# LMD18200_24.net
KiCad netlist of a schematic drawn in EAGLE
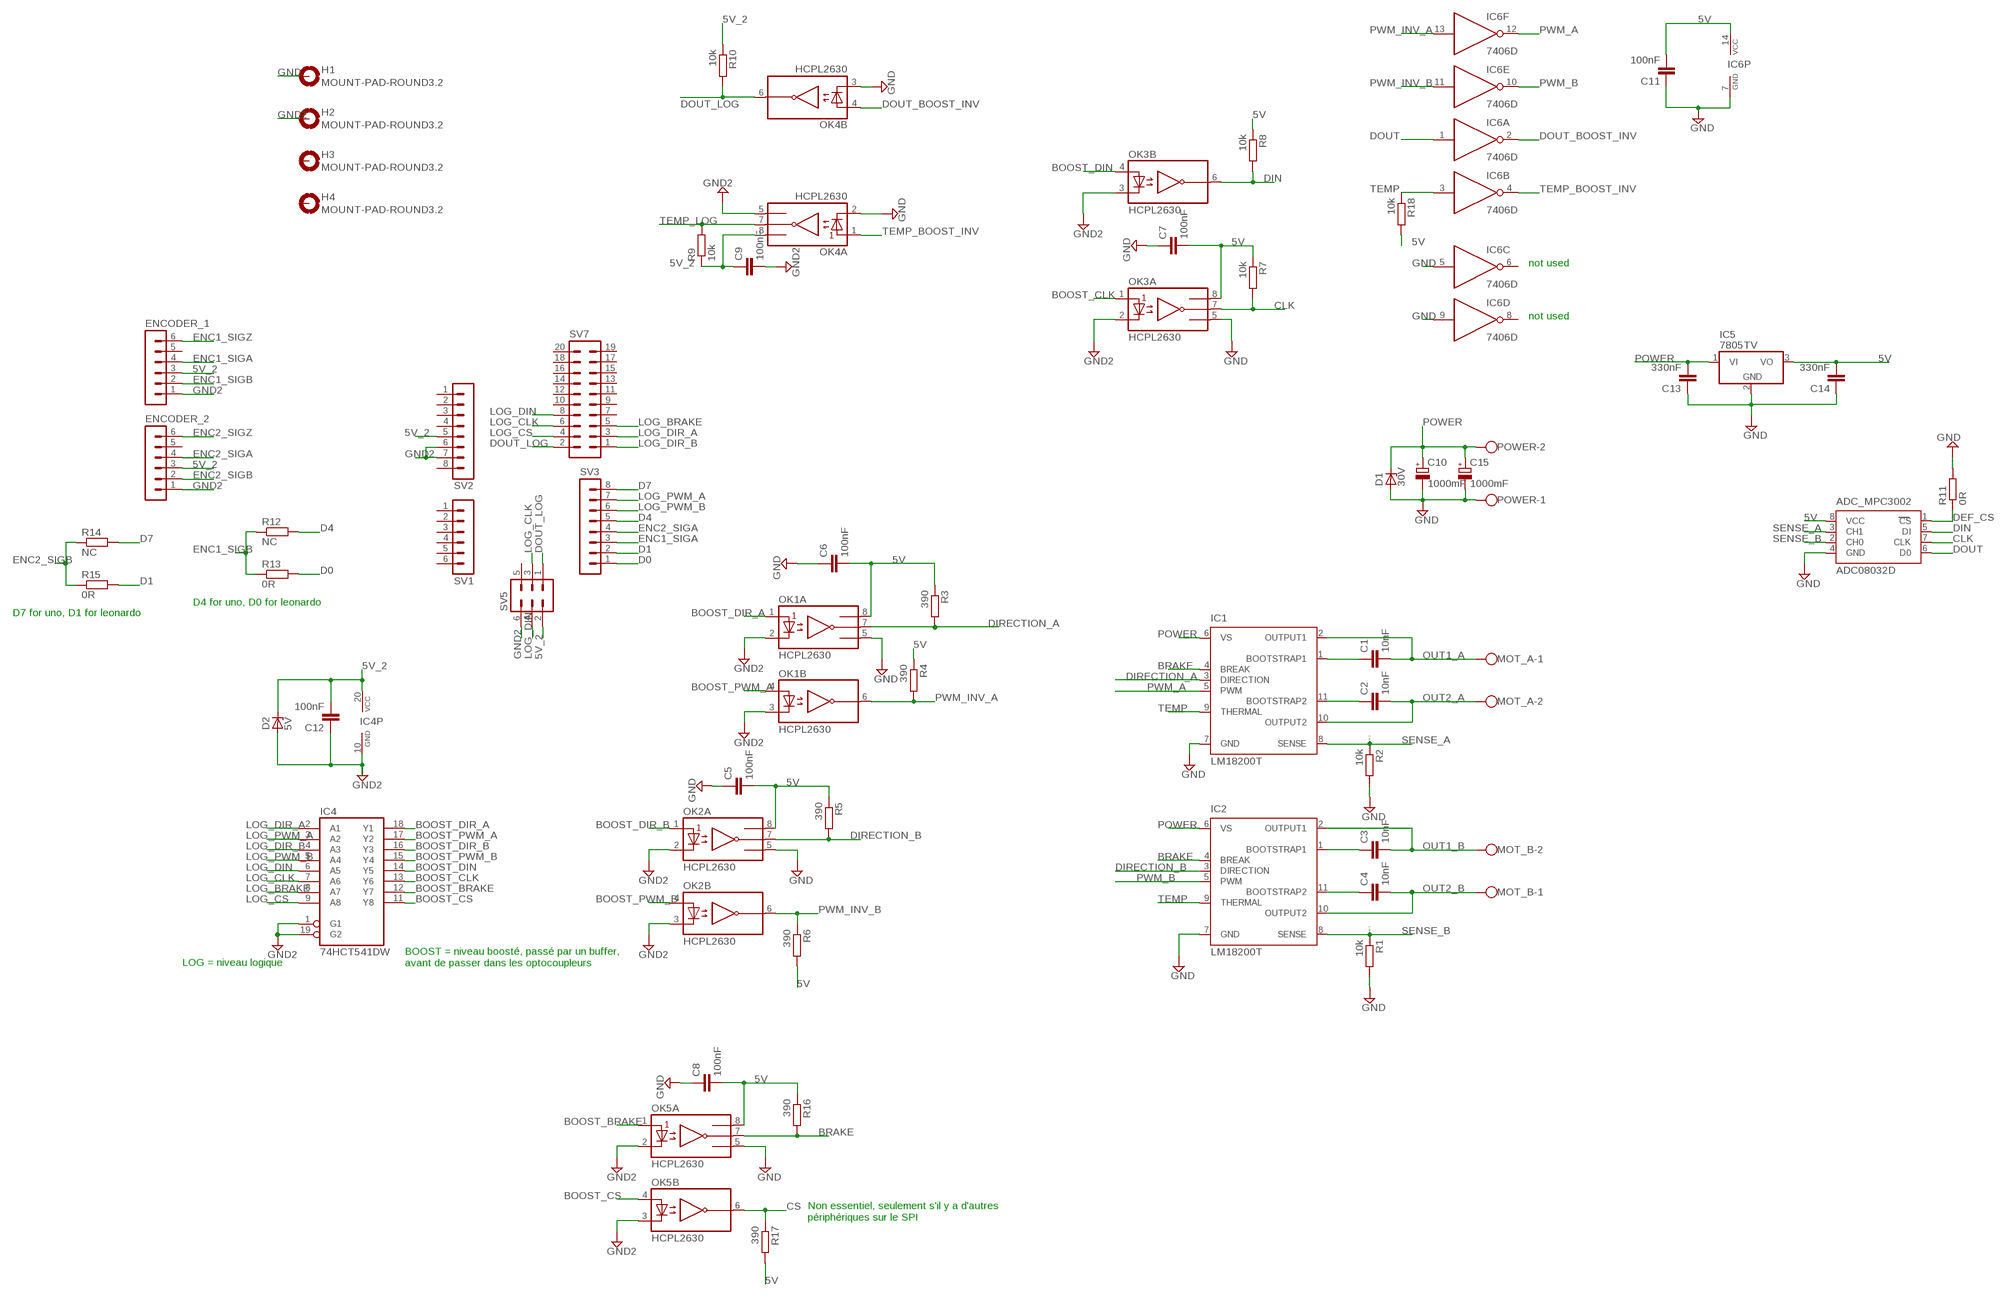
[diagram p0: schematic, sheet 1]

(export (version "E")
  (design (tool "Eeschema 10.0.6"))
  (components
    (comp (ref "ADC_MPC3002")
      (value "ADC08032D")
      (footprint "eagle-import:SO08")
      (libsource (lib "eagle-import") (part "ADC08032D"))
    )
    (comp (ref "C1")
      (value "10nF")
      (footprint "eagle-import:C2.5-2")
      (libsource (lib "eagle-import") (part "C2.5/2"))
    )
    (comp (ref "C2")
      (value "10nF")
      (footprint "eagle-import:C2.5-2")
      (libsource (lib "eagle-import") (part "C2.5/2"))
    )
    (comp (ref "C3")
      (value "10nF")
      (footprint "eagle-import:C2.5-2")
      (libsource (lib "eagle-import") (part "C2.5/2"))
    )
    (comp (ref "C4")
      (value "10nF")
      (footprint "eagle-import:C2.5-2")
      (libsource (lib "eagle-import") (part "C2.5/2"))
    )
    (comp (ref "C5")
      (value "100nF")
      (footprint "eagle-import:C2.5-2")
      (libsource (lib "eagle-import") (part "C2.5/2"))
    )
    (comp (ref "C6")
      (value "100nF")
      (footprint "eagle-import:C2.5-2")
      (libsource (lib "eagle-import") (part "C2.5/2"))
    )
    (comp (ref "C7")
      (value "100nF")
      (footprint "eagle-import:C2.5-2")
      (libsource (lib "eagle-import") (part "C2.5/2"))
    )
    (comp (ref "C8")
      (value "100nF")
      (footprint "eagle-import:C2.5-2")
      (libsource (lib "eagle-import") (part "C2.5/2"))
    )
    (comp (ref "C9")
      (value "100nF")
      (footprint "eagle-import:C2.5-2")
      (libsource (lib "eagle-import") (part "C2.5/2"))
    )
    (comp (ref "C10")
      (value "1000mF")
      (footprint "eagle-import:E5-13")
      (libsource (lib "eagle-import") (part "CPOL-EUE5-13"))
    )
    (comp (ref "C11")
      (value "100nF")
      (footprint "eagle-import:C0805")
      (libsource (lib "eagle-import") (part "C-EUC0805"))
    )
    (comp (ref "C12")
      (value "100nF")
      (footprint "eagle-import:C2.5-2")
      (libsource (lib "eagle-import") (part "C2.5/2"))
    )
    (comp (ref "C13")
      (value "330nF")
      (footprint "eagle-import:C2.5-2")
      (libsource (lib "eagle-import") (part "C2.5/2"))
    )
    (comp (ref "C14")
      (value "330nF")
      (footprint "eagle-import:C2.5-2")
      (libsource (lib "eagle-import") (part "C2.5/2"))
    )
    (comp (ref "C15")
      (value "1000mF")
      (footprint "eagle-import:E5-13")
      (libsource (lib "eagle-import") (part "CPOL-EUE5-13"))
    )
    (comp (ref "D1")
      (value "30V")
      (footprint "eagle-import:SOD80C")
      (libsource (lib "eagle-import") (part "ZENER-DIODESOD80C"))
    )
    (comp (ref "D2")
      (value "5V")
      (footprint "eagle-import:SOD80C")
      (libsource (lib "eagle-import") (part "ZENER-DIODESOD80C"))
    )
    (comp (ref "ENCODER_1")
      (value "MA06-1")
      (footprint "eagle-import:MA06-1")
      (libsource (lib "eagle-import") (part "MA06-1"))
    )
    (comp (ref "ENCODER_2")
      (value "MA06-1")
      (footprint "eagle-import:MA06-1")
      (libsource (lib "eagle-import") (part "MA06-1"))
    )
    (comp (ref "H1")
      (value "MOUNT-PAD-ROUND3.2")
      (footprint "eagle-import:3,2-PAD")
      (libsource (lib "eagle-import") (part "MOUNT-PAD-ROUND3.2"))
    )
    (comp (ref "H2")
      (value "MOUNT-PAD-ROUND3.2")
      (footprint "eagle-import:3,2-PAD")
      (libsource (lib "eagle-import") (part "MOUNT-PAD-ROUND3.2"))
    )
    (comp (ref "H3")
      (value "MOUNT-PAD-ROUND3.2")
      (footprint "eagle-import:3,2-PAD")
      (libsource (lib "eagle-import") (part "MOUNT-PAD-ROUND3.2"))
    )
    (comp (ref "H4")
      (value "MOUNT-PAD-ROUND3.2")
      (footprint "eagle-import:3,2-PAD")
      (libsource (lib "eagle-import") (part "MOUNT-PAD-ROUND3.2"))
    )
    (comp (ref "IC1")
      (value "LM18200T")
      (footprint "eagle-import:TO-220-11")
      (libsource (lib "eagle-import") (part "LM18200T"))
    )
    (comp (ref "IC2")
      (value "LM18200T")
      (footprint "eagle-import:TO-220-11")
      (libsource (lib "eagle-import") (part "LM18200T"))
    )
    (comp (ref "IC4")
      (value "74HCT541DW")
      (footprint "eagle-import:SO20W")
      (libsource (lib "eagle-import") (part "74541DWHCT"))
    )
    (comp (ref "IC5")
      (value "7805TV")
      (footprint "eagle-import:TO220V")
      (libsource (lib "eagle-import") (part "78TV05"))
    )
    (comp (ref "IC6")
      (value "7406D")
      (footprint "eagle-import:SO14")
      (libsource (lib "eagle-import") (part "7406D"))
    )
    (comp (ref "MOT_A")
      (value "W237-102")
      (footprint "eagle-import:W237-102")
      (fields (field (name "MPN") "237-102"))
      (libsource (lib "eagle-import") (part "W237-102"))
    )
    (comp (ref "MOT_B")
      (value "W237-102")
      (footprint "eagle-import:W237-102")
      (fields (field (name "MPN") "237-102"))
      (libsource (lib "eagle-import") (part "W237-102"))
    )
    (comp (ref "OK1")
      (value "HCPL2630")
      (footprint "eagle-import:DIL08")
      (fields (field (name "MF") "AGILENT TECHNOLOGIES") (field (name "MPN") "HCPL-2630-000E"))
      (libsource (lib "eagle-import") (part "HCPL2630"))
    )
    (comp (ref "OK2")
      (value "HCPL2630")
      (footprint "eagle-import:DIL08")
      (fields (field (name "MF") "AGILENT TECHNOLOGIES") (field (name "MPN") "HCPL-2630-000E"))
      (libsource (lib "eagle-import") (part "HCPL2630"))
    )
    (comp (ref "OK3")
      (value "HCPL2630")
      (footprint "eagle-import:DIL08")
      (fields (field (name "MF") "AGILENT TECHNOLOGIES") (field (name "MPN") "HCPL-2630-000E"))
      (libsource (lib "eagle-import") (part "HCPL2630"))
    )
    (comp (ref "OK4")
      (value "HCPL2630")
      (footprint "eagle-import:DIL08")
      (fields (field (name "MF") "AGILENT TECHNOLOGIES") (field (name "MPN") "HCPL-2630-000E"))
      (libsource (lib "eagle-import") (part "HCPL2630"))
    )
    (comp (ref "OK5")
      (value "HCPL2630")
      (footprint "eagle-import:DIL08")
      (fields (field (name "MF") "AGILENT TECHNOLOGIES") (field (name "MPN") "HCPL-2630-000E"))
      (libsource (lib "eagle-import") (part "HCPL2630"))
    )
    (comp (ref "POWER")
      (value "W237-102")
      (footprint "eagle-import:W237-102")
      (fields (field (name "MPN") "237-102"))
      (libsource (lib "eagle-import") (part "W237-102"))
    )
    (comp (ref "R1")
      (value "10k")
      (footprint "eagle-import:R0805")
      (libsource (lib "eagle-import") (part "R"))
    )
    (comp (ref "R2")
      (value "10k")
      (footprint "eagle-import:R0805")
      (libsource (lib "eagle-import") (part "R"))
    )
    (comp (ref "R3")
      (value "390")
      (footprint "eagle-import:R0805")
      (libsource (lib "eagle-import") (part "R-EU_R0805"))
    )
    (comp (ref "R4")
      (value "390")
      (footprint "eagle-import:R0805")
      (libsource (lib "eagle-import") (part "R-EU_R0805"))
    )
    (comp (ref "R5")
      (value "390")
      (footprint "eagle-import:R0805")
      (libsource (lib "eagle-import") (part "R-EU_R0805"))
    )
    (comp (ref "R6")
      (value "390")
      (footprint "eagle-import:R0805")
      (libsource (lib "eagle-import") (part "R-EU_R0805"))
    )
    (comp (ref "R7")
      (value "10k")
      (footprint "eagle-import:R0805")
      (libsource (lib "eagle-import") (part "R-EU_R0805"))
    )
    (comp (ref "R8")
      (value "10k")
      (footprint "eagle-import:R0805")
      (libsource (lib "eagle-import") (part "R-EU_R0805"))
    )
    (comp (ref "R9")
      (value "10k")
      (footprint "eagle-import:R0805")
      (libsource (lib "eagle-import") (part "R-EU_R0805"))
    )
    (comp (ref "R10")
      (value "10k")
      (footprint "eagle-import:R0805")
      (libsource (lib "eagle-import") (part "R-EU_R0805"))
    )
    (comp (ref "R11")
      (value "0R")
      (footprint "eagle-import:R0805")
      (libsource (lib "eagle-import") (part "R"))
    )
    (comp (ref "R12")
      (value "NC")
      (footprint "eagle-import:R0805")
      (libsource (lib "eagle-import") (part "R-EU_R0805"))
    )
    (comp (ref "R13")
      (value "0R")
      (footprint "eagle-import:R0805")
      (libsource (lib "eagle-import") (part "R-EU_R0805"))
    )
    (comp (ref "R14")
      (value "NC")
      (footprint "eagle-import:R0805")
      (libsource (lib "eagle-import") (part "R-EU_R0805"))
    )
    (comp (ref "R15")
      (value "0R")
      (footprint "eagle-import:R0805")
      (libsource (lib "eagle-import") (part "R-EU_R0805"))
    )
    (comp (ref "R16")
      (value "390")
      (footprint "eagle-import:R0805")
      (libsource (lib "eagle-import") (part "R-EU_R0805"))
    )
    (comp (ref "R17")
      (value "390")
      (footprint "eagle-import:R0805")
      (libsource (lib "eagle-import") (part "R-EU_R0805"))
    )
    (comp (ref "R18")
      (value "10k")
      (footprint "eagle-import:R0805")
      (libsource (lib "eagle-import") (part "R-EU_R0805"))
    )
    (comp (ref "SV1")
      (value "MA06-1")
      (footprint "eagle-import:MA06-1")
      (libsource (lib "eagle-import") (part "MA06-1"))
    )
    (comp (ref "SV2")
      (value "MA08-1")
      (footprint "eagle-import:MA08-1")
      (libsource (lib "eagle-import") (part "MA08-1"))
    )
    (comp (ref "SV3")
      (value "MA08-1")
      (footprint "eagle-import:MA08-1")
      (libsource (lib "eagle-import") (part "MA08-1"))
    )
    (comp (ref "SV5")
      (value "MA03-2")
      (footprint "eagle-import:MA03-2")
      (libsource (lib "eagle-import") (part "MA03-2"))
    )
    (comp (ref "SV7")
      (value "MA10-2")
      (footprint "eagle-import:MA10-2")
      (libsource (lib "eagle-import") (part "MA10-2"))
    )
  )
  (nets
    (net (code "1") (name "/5V") (class "Default")
      (node (ref "ADC_MPC3002") (pin "8") (pinfunction "VCC_8") (pintype "power_in"))
      (node (ref "C11") (pin "2") (pinfunction "2_2") (pintype "passive"))
      (node (ref "C14") (pin "2") (pinfunction "2_2") (pintype "passive"))
      (node (ref "C5") (pin "2") (pinfunction "2_2") (pintype "passive"))
      (node (ref "C6") (pin "2") (pinfunction "2_2") (pintype "passive"))
      (node (ref "C7") (pin "2") (pinfunction "2_2") (pintype "passive"))
      (node (ref "C8") (pin "2") (pinfunction "2_2") (pintype "passive"))
      (node (ref "IC5") (pin "3") (pinfunction "VO_3") (pintype "passive"))
      (node (ref "IC6") (pin "14") (pinfunction "VCC_14") (pintype "power_in"))
      (node (ref "OK1") (pin "8") (pinfunction "VCC_8") (pintype "passive"))
      (node (ref "OK2") (pin "8") (pinfunction "VCC_8") (pintype "passive"))
      (node (ref "OK3") (pin "8") (pinfunction "VCC_8") (pintype "passive"))
      (node (ref "OK5") (pin "8") (pinfunction "VCC_8") (pintype "passive"))
      (node (ref "R16") (pin "1") (pinfunction "1_1") (pintype "passive"))
      (node (ref "R17") (pin "2") (pinfunction "2_2") (pintype "passive"))
      (node (ref "R18") (pin "2") (pinfunction "2_2") (pintype "passive"))
      (node (ref "R3") (pin "1") (pinfunction "1_1") (pintype "passive"))
      (node (ref "R4") (pin "1") (pinfunction "1_1") (pintype "passive"))
      (node (ref "R5") (pin "1") (pinfunction "1_1") (pintype "passive"))
      (node (ref "R6") (pin "2") (pinfunction "2_2") (pintype "passive"))
      (node (ref "R7") (pin "1") (pinfunction "1_1") (pintype "passive"))
      (node (ref "R8") (pin "1") (pinfunction "1_1") (pintype "passive"))
    )
    (net (code "2") (name "/5V_2") (class "Default")
      (node (ref "C12") (pin "2") (pinfunction "2_2") (pintype "passive"))
      (node (ref "C9") (pin "1") (pinfunction "1_1") (pintype "passive"))
      (node (ref "D2") (pin "C") (pinfunction "C_C") (pintype "passive"))
      (node (ref "ENCODER_1") (pin "3") (pinfunction "3_3") (pintype "passive"))
      (node (ref "ENCODER_2") (pin "3") (pinfunction "3_3") (pintype "passive"))
      (node (ref "IC4") (pin "20") (pinfunction "VCC_20") (pintype "power_in"))
      (node (ref "OK4") (pin "8") (pinfunction "VCC_8") (pintype "passive"))
      (node (ref "R10") (pin "1") (pinfunction "1_1") (pintype "passive"))
      (node (ref "R9") (pin "1") (pinfunction "1_1") (pintype "passive"))
      (node (ref "SV2") (pin "5") (pinfunction "5_5") (pintype "passive"))
      (node (ref "SV5") (pin "2") (pinfunction "2_2") (pintype "passive"))
    )
    (net (code "3") (name "/BOOST_BRAKE") (class "Default")
      (node (ref "IC4") (pin "12") (pinfunction "Y7_12") (pintype "tri_state"))
      (node (ref "OK5") (pin "1") (pinfunction "A1_1") (pintype "passive"))
    )
    (net (code "4") (name "/BOOST_CLK") (class "Default")
      (node (ref "IC4") (pin "13") (pinfunction "Y6_13") (pintype "tri_state"))
      (node (ref "OK3") (pin "1") (pinfunction "A1_1") (pintype "passive"))
    )
    (net (code "5") (name "/BOOST_CS") (class "Default")
      (node (ref "IC4") (pin "11") (pinfunction "Y8_11") (pintype "tri_state"))
      (node (ref "OK5") (pin "4") (pinfunction "A2_4") (pintype "passive"))
    )
    (net (code "6") (name "/BOOST_DIN") (class "Default")
      (node (ref "IC4") (pin "14") (pinfunction "Y5_14") (pintype "tri_state"))
      (node (ref "OK3") (pin "4") (pinfunction "A2_4") (pintype "passive"))
    )
    (net (code "7") (name "/BOOST_DIR_A") (class "Default")
      (node (ref "IC4") (pin "18") (pinfunction "Y1_18") (pintype "tri_state"))
      (node (ref "OK1") (pin "1") (pinfunction "A1_1") (pintype "passive"))
    )
    (net (code "8") (name "/BOOST_DIR_B") (class "Default")
      (node (ref "IC4") (pin "16") (pinfunction "Y3_16") (pintype "tri_state"))
      (node (ref "OK2") (pin "1") (pinfunction "A1_1") (pintype "passive"))
    )
    (net (code "9") (name "/BOOST_PWM_A") (class "Default")
      (node (ref "IC4") (pin "17") (pinfunction "Y2_17") (pintype "tri_state"))
      (node (ref "OK1") (pin "4") (pinfunction "A2_4") (pintype "passive"))
    )
    (net (code "10") (name "/BOOST_PWM_B") (class "Default")
      (node (ref "IC4") (pin "15") (pinfunction "Y4_15") (pintype "tri_state"))
      (node (ref "OK2") (pin "4") (pinfunction "A2_4") (pintype "passive"))
    )
    (net (code "11") (name "/BRAKE") (class "Default")
      (node (ref "IC1") (pin "4") (pinfunction "BREAK_4") (pintype "input"))
      (node (ref "IC2") (pin "4") (pinfunction "BREAK_4") (pintype "input"))
      (node (ref "OK5") (pin "7") (pinfunction "VO1_7") (pintype "passive"))
      (node (ref "R16") (pin "2") (pinfunction "2_2") (pintype "passive"))
    )
    (net (code "12") (name "/CLK") (class "Default")
      (node (ref "ADC_MPC3002") (pin "7") (pinfunction "CLK_7") (pintype "input"))
      (node (ref "OK3") (pin "7") (pinfunction "VO1_7") (pintype "passive"))
      (node (ref "R7") (pin "2") (pinfunction "2_2") (pintype "passive"))
    )
    (net (code "13") (name "/CS") (class "Default")
      (node (ref "OK5") (pin "6") (pinfunction "VO2_6") (pintype "passive"))
      (node (ref "R17") (pin "1") (pinfunction "1_1") (pintype "passive"))
    )
    (net (code "14") (name "/D0") (class "Default")
      (node (ref "R13") (pin "2") (pinfunction "2_2") (pintype "passive"))
      (node (ref "SV3") (pin "1") (pinfunction "1_1") (pintype "passive"))
    )
    (net (code "15") (name "/D1") (class "Default")
      (node (ref "R15") (pin "2") (pinfunction "2_2") (pintype "passive"))
      (node (ref "SV3") (pin "2") (pinfunction "2_2") (pintype "passive"))
    )
    (net (code "16") (name "/D4") (class "Default")
      (node (ref "R12") (pin "2") (pinfunction "2_2") (pintype "passive"))
      (node (ref "SV3") (pin "5") (pinfunction "5_5") (pintype "passive"))
    )
    (net (code "17") (name "/D7") (class "Default")
      (node (ref "R14") (pin "2") (pinfunction "2_2") (pintype "passive"))
      (node (ref "SV3") (pin "8") (pinfunction "8_8") (pintype "passive"))
    )
    (net (code "18") (name "/DEF_CS") (class "Default")
      (node (ref "ADC_MPC3002") (pin "1") (pinfunction "CS_1") (pintype "input"))
      (node (ref "R11") (pin "1") (pinfunction "1_1") (pintype "passive"))
    )
    (net (code "19") (name "/DIN") (class "Default")
      (node (ref "ADC_MPC3002") (pin "5") (pinfunction "DI_5") (pintype "input"))
      (node (ref "OK3") (pin "6") (pinfunction "VO2_6") (pintype "passive"))
      (node (ref "R8") (pin "2") (pinfunction "2_2") (pintype "passive"))
    )
    (net (code "20") (name "/DIRECTION_A") (class "Default")
      (node (ref "IC1") (pin "3") (pinfunction "DIRECTION_3") (pintype "input"))
      (node (ref "OK1") (pin "7") (pinfunction "VO1_7") (pintype "passive"))
      (node (ref "R3") (pin "2") (pinfunction "2_2") (pintype "passive"))
    )
    (net (code "21") (name "/DIRECTION_B") (class "Default")
      (node (ref "IC2") (pin "3") (pinfunction "DIRECTION_3") (pintype "input"))
      (node (ref "OK2") (pin "7") (pinfunction "VO1_7") (pintype "passive"))
      (node (ref "R5") (pin "2") (pinfunction "2_2") (pintype "passive"))
    )
    (net (code "22") (name "/DOUT") (class "Default")
      (node (ref "ADC_MPC3002") (pin "6") (pinfunction "D0_6") (pintype "tri_state"))
      (node (ref "IC6") (pin "1") (pinfunction "I_1") (pintype "input"))
    )
    (net (code "23") (name "/DOUT_BOOST_INV") (class "Default")
      (node (ref "IC6") (pin "2") (pinfunction "O_2") (pintype "open_collector"))
      (node (ref "OK4") (pin "4") (pinfunction "A2_4") (pintype "passive"))
    )
    (net (code "24") (name "/DOUT_LOG") (class "Default")
      (node (ref "OK4") (pin "6") (pinfunction "VO2_6") (pintype "passive"))
      (node (ref "R10") (pin "2") (pinfunction "2_2") (pintype "passive"))
      (node (ref "SV5") (pin "1") (pinfunction "1_1") (pintype "passive"))
      (node (ref "SV7") (pin "2") (pinfunction "2_2") (pintype "passive"))
    )
    (net (code "25") (name "/ENC1_SIGA") (class "Default")
      (node (ref "ENCODER_1") (pin "4") (pinfunction "4_4") (pintype "passive"))
      (node (ref "SV3") (pin "3") (pinfunction "3_3") (pintype "passive"))
    )
    (net (code "26") (name "/ENC1_SIGB") (class "Default")
      (node (ref "ENCODER_1") (pin "2") (pinfunction "2_2") (pintype "passive"))
      (node (ref "R12") (pin "1") (pinfunction "1_1") (pintype "passive"))
      (node (ref "R13") (pin "1") (pinfunction "1_1") (pintype "passive"))
    )
    (net (code "27") (name "/ENC1_SIGZ") (class "Default")
      (node (ref "ENCODER_1") (pin "6") (pinfunction "6_6") (pintype "passive"))
    )
    (net (code "28") (name "/ENC2_SIGA") (class "Default")
      (node (ref "ENCODER_2") (pin "4") (pinfunction "4_4") (pintype "passive"))
      (node (ref "SV3") (pin "4") (pinfunction "4_4") (pintype "passive"))
    )
    (net (code "29") (name "/ENC2_SIGB") (class "Default")
      (node (ref "ENCODER_2") (pin "2") (pinfunction "2_2") (pintype "passive"))
      (node (ref "R14") (pin "1") (pinfunction "1_1") (pintype "passive"))
      (node (ref "R15") (pin "1") (pinfunction "1_1") (pintype "passive"))
    )
    (net (code "30") (name "/ENC2_SIGZ") (class "Default")
      (node (ref "ENCODER_2") (pin "6") (pinfunction "6_6") (pintype "passive"))
    )
    (net (code "31") (name "/LOG_BRAKE") (class "Default")
      (node (ref "IC4") (pin "8") (pinfunction "A7_8") (pintype "input"))
      (node (ref "SV7") (pin "5") (pinfunction "5_5") (pintype "passive"))
    )
    (net (code "32") (name "/LOG_CLK") (class "Default")
      (node (ref "IC4") (pin "7") (pinfunction "A6_7") (pintype "input"))
      (node (ref "SV5") (pin "3") (pinfunction "3_3") (pintype "passive"))
      (node (ref "SV7") (pin "6") (pinfunction "6_6") (pintype "passive"))
    )
    (net (code "33") (name "/LOG_CS") (class "Default")
      (node (ref "IC4") (pin "9") (pinfunction "A8_9") (pintype "input"))
      (node (ref "SV7") (pin "4") (pinfunction "4_4") (pintype "passive"))
    )
    (net (code "34") (name "/LOG_DIN") (class "Default")
      (node (ref "IC4") (pin "6") (pinfunction "A5_6") (pintype "input"))
      (node (ref "SV5") (pin "4") (pinfunction "4_4") (pintype "passive"))
      (node (ref "SV7") (pin "8") (pinfunction "8_8") (pintype "passive"))
    )
    (net (code "35") (name "/LOG_DIR_A") (class "Default")
      (node (ref "IC4") (pin "2") (pinfunction "A1_2") (pintype "input"))
      (node (ref "SV7") (pin "3") (pinfunction "3_3") (pintype "passive"))
    )
    (net (code "36") (name "/LOG_DIR_B") (class "Default")
      (node (ref "IC4") (pin "4") (pinfunction "A3_4") (pintype "input"))
      (node (ref "SV7") (pin "1") (pinfunction "1_1") (pintype "passive"))
    )
    (net (code "37") (name "/LOG_PWM_A") (class "Default")
      (node (ref "IC4") (pin "3") (pinfunction "A2_3") (pintype "input"))
      (node (ref "SV3") (pin "7") (pinfunction "7_7") (pintype "passive"))
    )
    (net (code "38") (name "/LOG_PWM_B") (class "Default")
      (node (ref "IC4") (pin "5") (pinfunction "A4_5") (pintype "input"))
      (node (ref "SV3") (pin "6") (pinfunction "6_6") (pintype "passive"))
    )
    (net (code "39") (name "/OUT1_A") (class "Default")
      (node (ref "C1") (pin "2") (pinfunction "2_2") (pintype "passive"))
      (node (ref "IC1") (pin "2") (pinfunction "OUTPUT1_2") (pintype "output"))
      (node (ref "MOT_A") (pin "1") (pinfunction "KL_1") (pintype "passive"))
    )
    (net (code "40") (name "/OUT1_B") (class "Default")
      (node (ref "C3") (pin "2") (pinfunction "2_2") (pintype "passive"))
      (node (ref "IC2") (pin "2") (pinfunction "OUTPUT1_2") (pintype "output"))
      (node (ref "MOT_B") (pin "2") (pinfunction "KL_2") (pintype "passive"))
    )
    (net (code "41") (name "/OUT2_A") (class "Default")
      (node (ref "C2") (pin "2") (pinfunction "2_2") (pintype "passive"))
      (node (ref "IC1") (pin "10") (pinfunction "OUTPUT2_10") (pintype "output"))
      (node (ref "MOT_A") (pin "2") (pinfunction "KL_2") (pintype "passive"))
    )
    (net (code "42") (name "/OUT2_B") (class "Default")
      (node (ref "C4") (pin "2") (pinfunction "2_2") (pintype "passive"))
      (node (ref "IC2") (pin "10") (pinfunction "OUTPUT2_10") (pintype "output"))
      (node (ref "MOT_B") (pin "1") (pinfunction "KL_1") (pintype "passive"))
    )
    (net (code "43") (name "/POWER") (class "Default")
      (node (ref "C10") (pin "+") (pinfunction "+_+") (pintype "passive"))
      (node (ref "C13") (pin "2") (pinfunction "2_2") (pintype "passive"))
      (node (ref "C15") (pin "+") (pinfunction "+_+") (pintype "passive"))
      (node (ref "D1") (pin "C") (pinfunction "C_C") (pintype "passive"))
      (node (ref "IC1") (pin "6") (pinfunction "VS_6") (pintype "power_in"))
      (node (ref "IC2") (pin "6") (pinfunction "VS_6") (pintype "power_in"))
      (node (ref "IC5") (pin "1") (pinfunction "VI_1") (pintype "input"))
      (node (ref "POWER") (pin "2") (pinfunction "KL_2") (pintype "passive"))
    )
    (net (code "44") (name "/PWM_A") (class "Default")
      (node (ref "IC1") (pin "5") (pinfunction "PWM_5") (pintype "input"))
      (node (ref "IC6") (pin "12") (pinfunction "O_12") (pintype "open_collector"))
    )
    (net (code "45") (name "/PWM_B") (class "Default")
      (node (ref "IC2") (pin "5") (pinfunction "PWM_5") (pintype "input"))
      (node (ref "IC6") (pin "10") (pinfunction "O_10") (pintype "open_collector"))
    )
    (net (code "46") (name "/PWM_INV_A") (class "Default")
      (node (ref "IC6") (pin "13") (pinfunction "I_13") (pintype "input"))
      (node (ref "OK1") (pin "6") (pinfunction "VO2_6") (pintype "passive"))
      (node (ref "R4") (pin "2") (pinfunction "2_2") (pintype "passive"))
    )
    (net (code "47") (name "/PWM_INV_B") (class "Default")
      (node (ref "IC6") (pin "11") (pinfunction "I_11") (pintype "input"))
      (node (ref "OK2") (pin "6") (pinfunction "VO2_6") (pintype "passive"))
      (node (ref "R6") (pin "1") (pinfunction "1_1") (pintype "passive"))
    )
    (net (code "48") (name "/SENSE_A") (class "Default")
      (node (ref "ADC_MPC3002") (pin "3") (pinfunction "CH1_3") (pintype "input"))
      (node (ref "IC1") (pin "8") (pinfunction "SENSE_8") (pintype "output"))
      (node (ref "R2") (pin "1") (pinfunction "1_1") (pintype "passive"))
    )
    (net (code "49") (name "/SENSE_B") (class "Default")
      (node (ref "ADC_MPC3002") (pin "2") (pinfunction "CH0_2") (pintype "input"))
      (node (ref "IC2") (pin "8") (pinfunction "SENSE_8") (pintype "output"))
      (node (ref "R1") (pin "1") (pinfunction "1_1") (pintype "passive"))
    )
    (net (code "50") (name "/TEMP") (class "Default")
      (node (ref "IC1") (pin "9") (pinfunction "THERMAL_9") (pintype "output"))
      (node (ref "IC2") (pin "9") (pinfunction "THERMAL_9") (pintype "output"))
      (node (ref "IC6") (pin "3") (pinfunction "I_3") (pintype "input"))
      (node (ref "R18") (pin "1") (pinfunction "1_1") (pintype "passive"))
    )
    (net (code "51") (name "/TEMP_BOOST_INV") (class "Default")
      (node (ref "IC6") (pin "4") (pinfunction "O_4") (pintype "open_collector"))
      (node (ref "OK4") (pin "1") (pinfunction "A1_1") (pintype "passive"))
    )
    (net (code "52") (name "/TEMP_LOG") (class "Default")
      (node (ref "OK4") (pin "7") (pinfunction "VO1_7") (pintype "passive"))
      (node (ref "R9") (pin "2") (pinfunction "2_2") (pintype "passive"))
    )
    (net (code "53") (name "GND") (class "Default")
      (node (ref "ADC_MPC3002") (pin "4") (pinfunction "GND_4") (pintype "power_in"))
      (node (ref "C10") (pin "-") (pinfunction "-_-") (pintype "passive"))
      (node (ref "C11") (pin "1") (pinfunction "1_1") (pintype "passive"))
      (node (ref "C13") (pin "1") (pinfunction "1_1") (pintype "passive"))
      (node (ref "C14") (pin "1") (pinfunction "1_1") (pintype "passive"))
      (node (ref "C15") (pin "-") (pinfunction "-_-") (pintype "passive"))
      (node (ref "C5") (pin "1") (pinfunction "1_1") (pintype "passive"))
      (node (ref "C6") (pin "1") (pinfunction "1_1") (pintype "passive"))
      (node (ref "C7") (pin "1") (pinfunction "1_1") (pintype "passive"))
      (node (ref "C8") (pin "1") (pinfunction "1_1") (pintype "passive"))
      (node (ref "D1") (pin "A") (pinfunction "A_A") (pintype "passive"))
      (node (ref "H1") (pin "B3,2") (pinfunction "MOUNT_B3,2") (pintype "passive"))
      (node (ref "IC1") (pin "7") (pinfunction "GND_7") (pintype "power_in"))
      (node (ref "IC2") (pin "7") (pinfunction "GND_7") (pintype "power_in"))
      (node (ref "IC5") (pin "2") (pinfunction "GND_2") (pintype "passive"))
      (node (ref "IC6") (pin "5") (pinfunction "I_5") (pintype "input"))
      (node (ref "IC6") (pin "7") (pinfunction "GND_7") (pintype "power_in"))
      (node (ref "IC6") (pin "9") (pinfunction "I_9") (pintype "input"))
      (node (ref "OK1") (pin "5") (pinfunction "GND_5") (pintype "passive"))
      (node (ref "OK2") (pin "5") (pinfunction "GND_5") (pintype "passive"))
      (node (ref "OK3") (pin "5") (pinfunction "GND_5") (pintype "passive"))
      (node (ref "OK4") (pin "2") (pinfunction "C1_2") (pintype "passive"))
      (node (ref "OK4") (pin "3") (pinfunction "C2_3") (pintype "passive"))
      (node (ref "OK5") (pin "5") (pinfunction "GND_5") (pintype "passive"))
      (node (ref "POWER") (pin "1") (pinfunction "KL_1") (pintype "passive"))
      (node (ref "R1") (pin "2") (pinfunction "2_2") (pintype "passive"))
      (node (ref "R11") (pin "2") (pinfunction "2_2") (pintype "passive"))
      (node (ref "R2") (pin "2") (pinfunction "2_2") (pintype "passive"))
    )
    (net (code "54") (name "GND2") (class "Default")
      (node (ref "C12") (pin "1") (pinfunction "1_1") (pintype "passive"))
      (node (ref "C9") (pin "2") (pinfunction "2_2") (pintype "passive"))
      (node (ref "D2") (pin "A") (pinfunction "A_A") (pintype "passive"))
      (node (ref "ENCODER_1") (pin "1") (pinfunction "1_1") (pintype "passive"))
      (node (ref "ENCODER_2") (pin "1") (pinfunction "1_1") (pintype "passive"))
      (node (ref "H2") (pin "B3,2") (pinfunction "MOUNT_B3,2") (pintype "passive"))
      (node (ref "IC4") (pin "1") (pinfunction "G1_1") (pintype "input"))
      (node (ref "IC4") (pin "10") (pinfunction "GND_10") (pintype "power_in"))
      (node (ref "IC4") (pin "19") (pinfunction "G2_19") (pintype "input"))
      (node (ref "OK1") (pin "2") (pinfunction "C1_2") (pintype "passive"))
      (node (ref "OK1") (pin "3") (pinfunction "C2_3") (pintype "passive"))
      (node (ref "OK2") (pin "2") (pinfunction "C1_2") (pintype "passive"))
      (node (ref "OK2") (pin "3") (pinfunction "C2_3") (pintype "passive"))
      (node (ref "OK3") (pin "2") (pinfunction "C1_2") (pintype "passive"))
      (node (ref "OK3") (pin "3") (pinfunction "C2_3") (pintype "passive"))
      (node (ref "OK4") (pin "5") (pinfunction "GND_5") (pintype "passive"))
      (node (ref "OK5") (pin "2") (pinfunction "C1_2") (pintype "passive"))
      (node (ref "OK5") (pin "3") (pinfunction "C2_3") (pintype "passive"))
      (node (ref "SV2") (pin "6") (pinfunction "6_6") (pintype "passive"))
      (node (ref "SV2") (pin "7") (pinfunction "7_7") (pintype "passive"))
      (node (ref "SV5") (pin "6") (pinfunction "6_6") (pintype "passive"))
    )
    (net (code "55") (name "Net-(IC1-BOOTSTRAP1)") (class "Default")
      (node (ref "C1") (pin "1") (pinfunction "1_1") (pintype "passive"))
      (node (ref "IC1") (pin "1") (pinfunction "BOOTSTRAP1_1") (pintype "input"))
    )
    (net (code "56") (name "Net-(IC1-BOOTSTRAP2)") (class "Default")
      (node (ref "C2") (pin "1") (pinfunction "1_1") (pintype "passive"))
      (node (ref "IC1") (pin "11") (pinfunction "BOOTSTRAP2_11") (pintype "input"))
    )
    (net (code "57") (name "Net-(IC2-BOOTSTRAP1)") (class "Default")
      (node (ref "C3") (pin "1") (pinfunction "1_1") (pintype "passive"))
      (node (ref "IC2") (pin "1") (pinfunction "BOOTSTRAP1_1") (pintype "input"))
    )
    (net (code "58") (name "Net-(IC2-BOOTSTRAP2)") (class "Default")
      (node (ref "C4") (pin "1") (pinfunction "1_1") (pintype "passive"))
      (node (ref "IC2") (pin "11") (pinfunction "BOOTSTRAP2_11") (pintype "input"))
    )
    (net (code "59") (name "unconnected-(ENCODER_1-Pad5)") (class "Default")
      (node (ref "ENCODER_1") (pin "5") (pinfunction "5_5") (pintype "passive"))
    )
    (net (code "60") (name "unconnected-(ENCODER_2-Pad5)") (class "Default")
      (node (ref "ENCODER_2") (pin "5") (pinfunction "5_5") (pintype "passive"))
    )
    (net (code "61") (name "unconnected-(H3-MOUNT-PadB3,2)") (class "Default")
      (node (ref "H3") (pin "B3,2") (pinfunction "MOUNT_B3,2") (pintype "passive"))
    )
    (net (code "62") (name "unconnected-(H4-MOUNT-PadB3,2)") (class "Default")
      (node (ref "H4") (pin "B3,2") (pinfunction "MOUNT_B3,2") (pintype "passive"))
    )
    (net (code "63") (name "unconnected-(IC6C-O-Pad6)") (class "Default")
      (node (ref "IC6") (pin "6") (pinfunction "O_6") (pintype "open_collector"))
    )
    (net (code "64") (name "unconnected-(IC6D-O-Pad8)") (class "Default")
      (node (ref "IC6") (pin "8") (pinfunction "O_8") (pintype "open_collector"))
    )
    (net (code "65") (name "unconnected-(SV1-Pad1)") (class "Default")
      (node (ref "SV1") (pin "1") (pinfunction "1_1") (pintype "passive"))
    )
    (net (code "66") (name "unconnected-(SV1-Pad2)") (class "Default")
      (node (ref "SV1") (pin "2") (pinfunction "2_2") (pintype "passive"))
    )
    (net (code "67") (name "unconnected-(SV1-Pad3)") (class "Default")
      (node (ref "SV1") (pin "3") (pinfunction "3_3") (pintype "passive"))
    )
    (net (code "68") (name "unconnected-(SV1-Pad4)") (class "Default")
      (node (ref "SV1") (pin "4") (pinfunction "4_4") (pintype "passive"))
    )
    (net (code "69") (name "unconnected-(SV1-Pad5)") (class "Default")
      (node (ref "SV1") (pin "5") (pinfunction "5_5") (pintype "passive"))
    )
    (net (code "70") (name "unconnected-(SV1-Pad6)") (class "Default")
      (node (ref "SV1") (pin "6") (pinfunction "6_6") (pintype "passive"))
    )
    (net (code "71") (name "unconnected-(SV2-Pad1)") (class "Default")
      (node (ref "SV2") (pin "1") (pinfunction "1_1") (pintype "passive"))
    )
    (net (code "72") (name "unconnected-(SV2-Pad2)") (class "Default")
      (node (ref "SV2") (pin "2") (pinfunction "2_2") (pintype "passive"))
    )
    (net (code "73") (name "unconnected-(SV2-Pad3)") (class "Default")
      (node (ref "SV2") (pin "3") (pinfunction "3_3") (pintype "passive"))
    )
    (net (code "74") (name "unconnected-(SV2-Pad4)") (class "Default")
      (node (ref "SV2") (pin "4") (pinfunction "4_4") (pintype "passive"))
    )
    (net (code "75") (name "unconnected-(SV2-Pad8)") (class "Default")
      (node (ref "SV2") (pin "8") (pinfunction "8_8") (pintype "passive"))
    )
    (net (code "76") (name "unconnected-(SV5-Pad5)") (class "Default")
      (node (ref "SV5") (pin "5") (pinfunction "5_5") (pintype "passive"))
    )
    (net (code "77") (name "unconnected-(SV7-Pad7)") (class "Default")
      (node (ref "SV7") (pin "7") (pinfunction "7_7") (pintype "passive"))
    )
    (net (code "78") (name "unconnected-(SV7-Pad9)") (class "Default")
      (node (ref "SV7") (pin "9") (pinfunction "9_9") (pintype "passive"))
    )
    (net (code "79") (name "unconnected-(SV7-Pad10)") (class "Default")
      (node (ref "SV7") (pin "10") (pinfunction "10_10") (pintype "passive"))
    )
    (net (code "80") (name "unconnected-(SV7-Pad11)") (class "Default")
      (node (ref "SV7") (pin "11") (pinfunction "11_11") (pintype "passive"))
    )
    (net (code "81") (name "unconnected-(SV7-Pad12)") (class "Default")
      (node (ref "SV7") (pin "12") (pinfunction "12_12") (pintype "passive"))
    )
    (net (code "82") (name "unconnected-(SV7-Pad13)") (class "Default")
      (node (ref "SV7") (pin "13") (pinfunction "13_13") (pintype "passive"))
    )
    (net (code "83") (name "unconnected-(SV7-Pad14)") (class "Default")
      (node (ref "SV7") (pin "14") (pinfunction "14_14") (pintype "passive"))
    )
    (net (code "84") (name "unconnected-(SV7-Pad15)") (class "Default")
      (node (ref "SV7") (pin "15") (pinfunction "15_15") (pintype "passive"))
    )
    (net (code "85") (name "unconnected-(SV7-Pad16)") (class "Default")
      (node (ref "SV7") (pin "16") (pinfunction "16_16") (pintype "passive"))
    )
    (net (code "86") (name "unconnected-(SV7-Pad17)") (class "Default")
      (node (ref "SV7") (pin "17") (pinfunction "17_17") (pintype "passive"))
    )
    (net (code "87") (name "unconnected-(SV7-Pad18)") (class "Default")
      (node (ref "SV7") (pin "18") (pinfunction "18_18") (pintype "passive"))
    )
    (net (code "88") (name "unconnected-(SV7-Pad19)") (class "Default")
      (node (ref "SV7") (pin "19") (pinfunction "19_19") (pintype "passive"))
    )
    (net (code "89") (name "unconnected-(SV7-Pad20)") (class "Default")
      (node (ref "SV7") (pin "20") (pinfunction "20_20") (pintype "passive"))
    )
  )
)
